# 141004_AriloTX_REV2_2_0_433MHZ_td.net
KiCad netlist of a schematic drawn in EAGLE
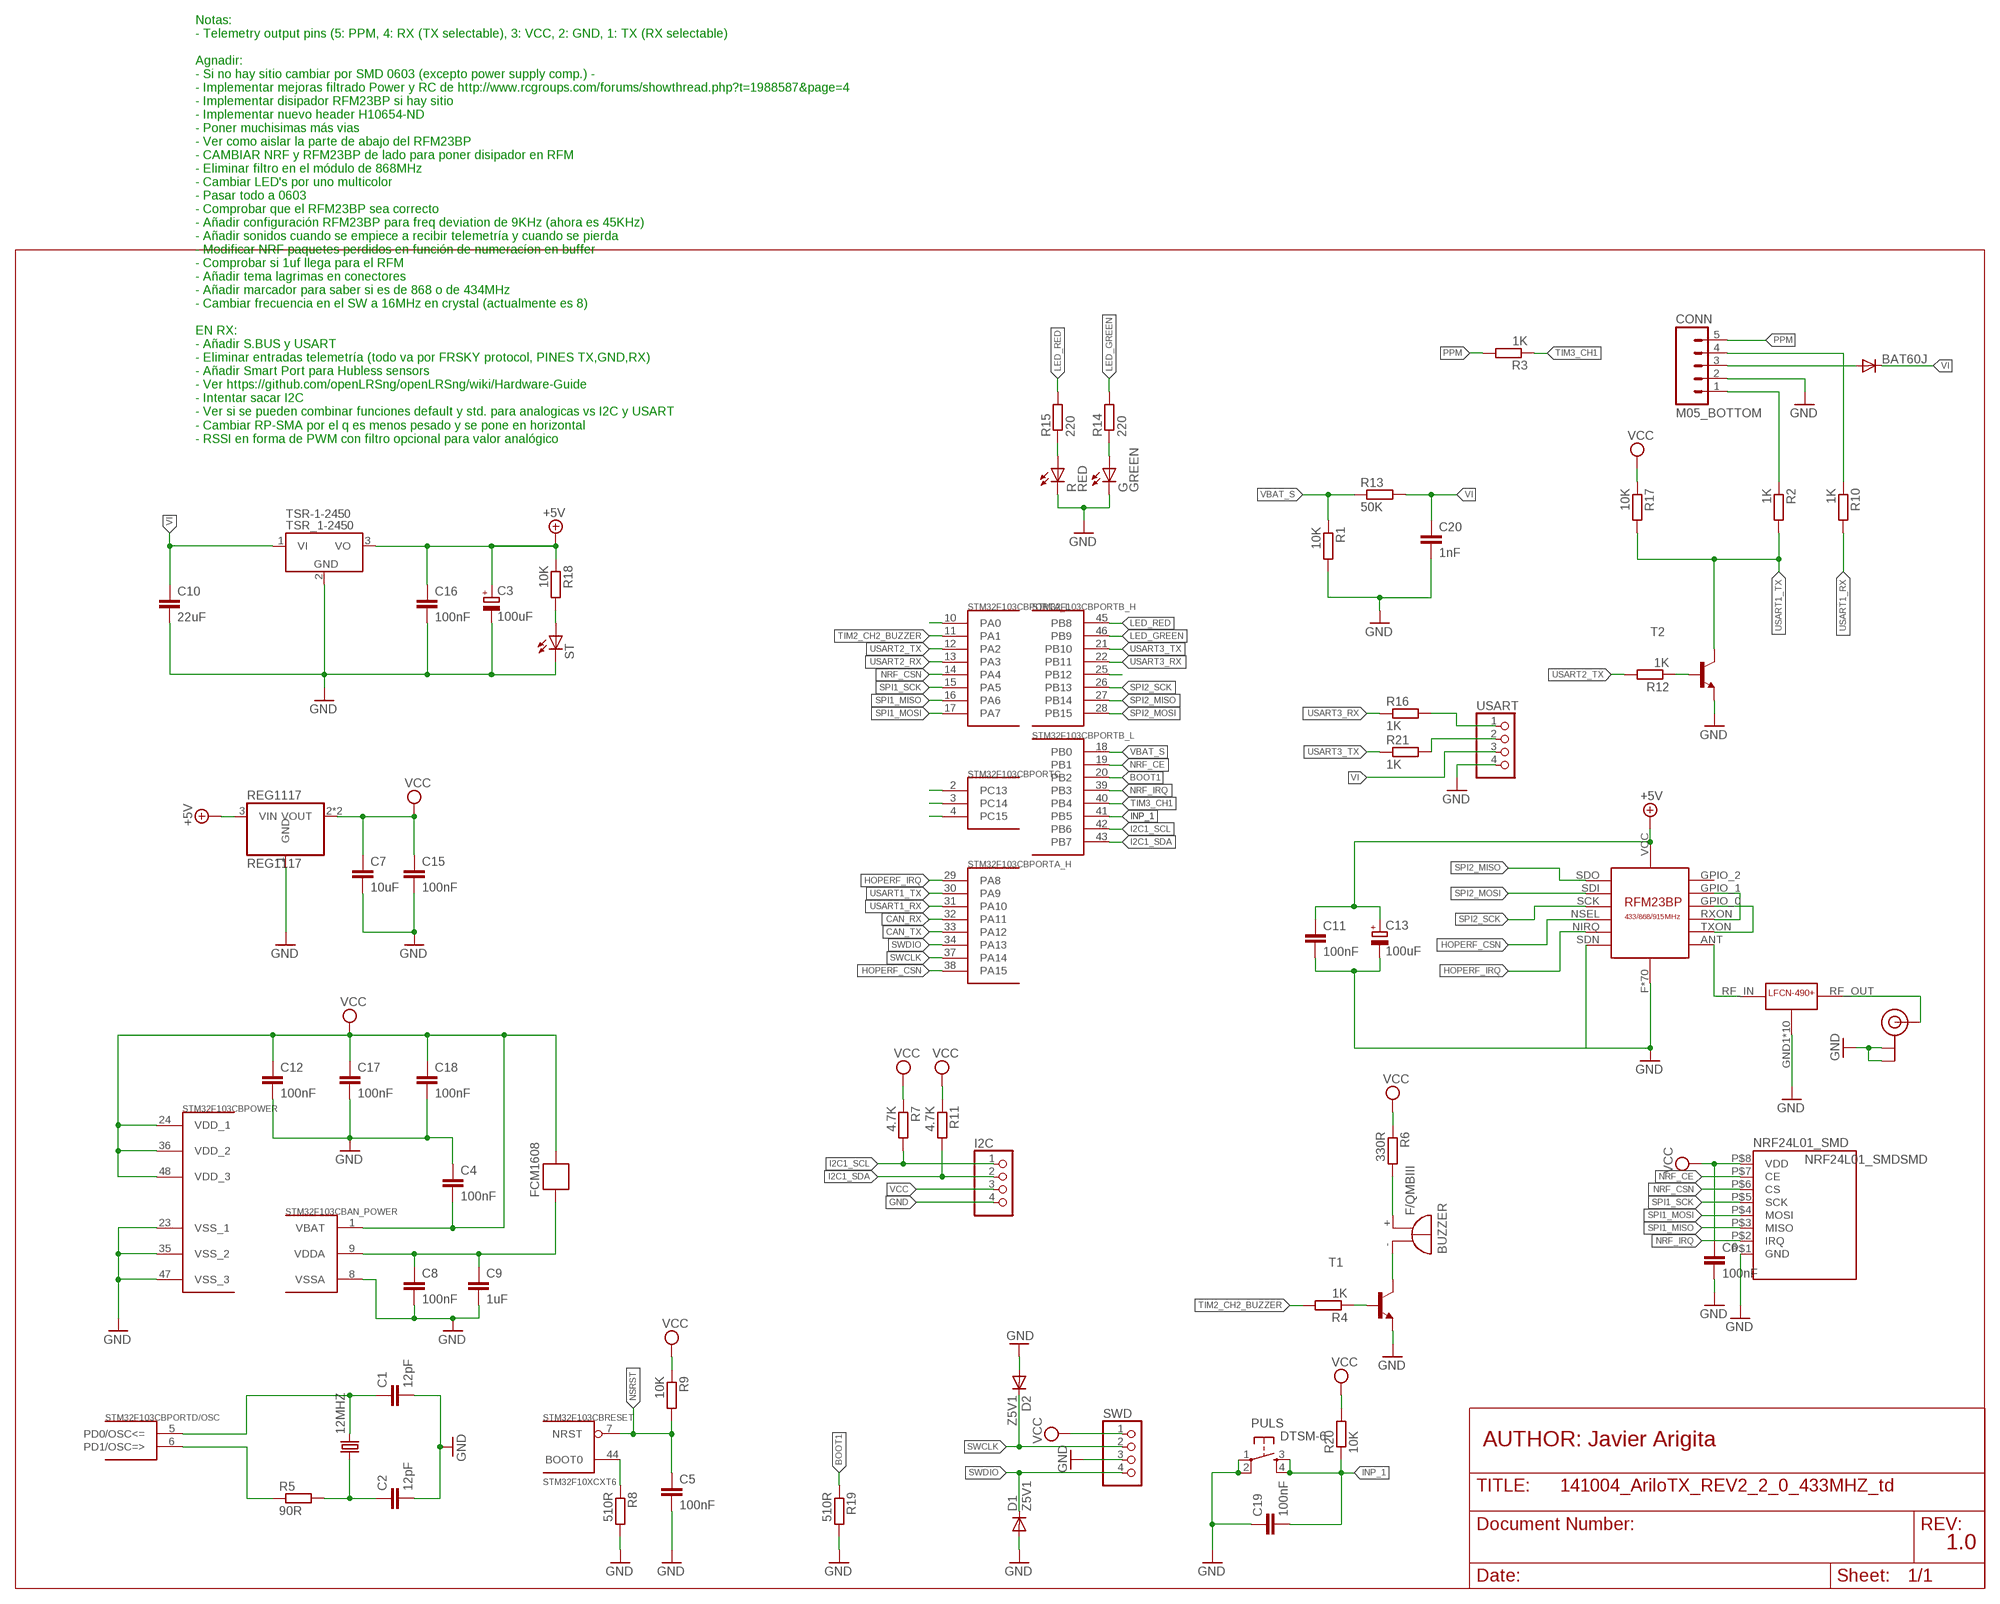
[diagram p0: schematic, sheet 1]

(export (version "E")
  (design (tool "Eeschema 10.0.6"))
  (components
    (comp (ref "12MHZ")
      (value "CRYSTAL5X3")
      (footprint "eagle-import:CRYSTAL-SMD-5X3")
      (libsource (lib "eagle-import") (part "CRYSTAL5X3"))
    )
    (comp (ref "BAT60J")
      (value "DIODE-SOD323-R")
      (footprint "eagle-import:SOD323-R")
      (libsource (lib "eagle-import") (part "DIODE-SOD323-R"))
    )
    (comp (ref "BUZZER")
      (value "F/QMBIII")
      (footprint "eagle-import:F_QMBIII")
      (libsource (lib "eagle-import") (part "F/QMBIII"))
    )
    (comp (ref "C1")
      (value "12pF")
      (footprint "eagle-import:C0603")
      (libsource (lib "eagle-import") (part "C-EUC0603"))
    )
    (comp (ref "C2")
      (value "12pF")
      (footprint "eagle-import:C0603")
      (libsource (lib "eagle-import") (part "C-EUC0603"))
    )
    (comp (ref "C3")
      (value "100uF")
      (footprint "eagle-import:SMC_B")
      (libsource (lib "eagle-import") (part "CPOL-EUSMCB"))
    )
    (comp (ref "C4")
      (value "100nF")
      (footprint "eagle-import:C0603")
      (libsource (lib "eagle-import") (part "C-EUC0603"))
    )
    (comp (ref "C5")
      (value "100nF")
      (footprint "eagle-import:C0603")
      (libsource (lib "eagle-import") (part "C-EUC0603"))
    )
    (comp (ref "C6")
      (value "100nF")
      (footprint "eagle-import:C0603")
      (libsource (lib "eagle-import") (part "C-EUC0603"))
    )
    (comp (ref "C7")
      (value "10uF")
      (footprint "eagle-import:C0805")
      (libsource (lib "eagle-import") (part "C-EUC0805"))
    )
    (comp (ref "C8")
      (value "100nF")
      (footprint "eagle-import:C0603")
      (libsource (lib "eagle-import") (part "C-EUC0603"))
    )
    (comp (ref "C9")
      (value "1uF")
      (footprint "eagle-import:C0603")
      (libsource (lib "eagle-import") (part "C-EUC0603"))
    )
    (comp (ref "C10")
      (value "22uF")
      (footprint "eagle-import:C3216")
      (libsource (lib "eagle-import") (part "resistor_C-EUC3216"))
    )
    (comp (ref "C11")
      (value "100nF")
      (footprint "eagle-import:C0603")
      (libsource (lib "eagle-import") (part "C-EUC0603"))
    )
    (comp (ref "C12")
      (value "100nF")
      (footprint "eagle-import:C0603")
      (libsource (lib "eagle-import") (part "C-EUC0603"))
    )
    (comp (ref "C13")
      (value "100uF")
      (footprint "eagle-import:SMC_B")
      (libsource (lib "eagle-import") (part "CPOL-EUSMCB"))
    )
    (comp (ref "C15")
      (value "100nF")
      (footprint "eagle-import:C0603")
      (libsource (lib "eagle-import") (part "C-EUC0603"))
    )
    (comp (ref "C16")
      (value "100nF")
      (footprint "eagle-import:C0603")
      (libsource (lib "eagle-import") (part "C-EUC0603"))
    )
    (comp (ref "C17")
      (value "100nF")
      (footprint "eagle-import:C0603")
      (libsource (lib "eagle-import") (part "C-EUC0603"))
    )
    (comp (ref "C18")
      (value "100nF")
      (footprint "eagle-import:C0603")
      (libsource (lib "eagle-import") (part "C-EUC0603"))
    )
    (comp (ref "C19")
      (value "100nF")
      (footprint "eagle-import:C0603")
      (libsource (lib "eagle-import") (part "C-EUC0603"))
    )
    (comp (ref "C20")
      (value "1nF")
      (footprint "eagle-import:C0603")
      (libsource (lib "eagle-import") (part "C-EUC0603"))
    )
    (comp (ref "CONN")
      (value "M05_BOTTOM")
      (footprint "eagle-import:M05_BOTTOM")
      (libsource (lib "eagle-import") (part "M05_BOTTOM"))
    )
    (comp (ref "D1")
      (value "Z5V1")
      (footprint "eagle-import:SOD323-R")
      (libsource (lib "eagle-import") (part "DIODE-SOD323-R"))
    )
    (comp (ref "D2")
      (value "Z5V1")
      (footprint "eagle-import:SOD323-R")
      (libsource (lib "eagle-import") (part "DIODE-SOD323-R"))
    )
    (comp (ref "FCM1608")
      (value "FERRITE-BEAD")
      (footprint "eagle-import:R0603")
      (libsource (lib "eagle-import") (part "FERRITE-BEAD"))
    )
    (comp (ref "G")
      (value "GREEN")
      (footprint "eagle-import:CHIP-LED0603")
      (libsource (lib "eagle-import") (part "LEDCHIP-LED0603"))
    )
    (comp (ref "I2C")
      (value "PINHD-1X4")
      (footprint "eagle-import:1X04")
      (libsource (lib "eagle-import") (part "PINHD-1X4"))
    )
    (comp (ref "LFCN490+")
      (value "LFCN490+")
      (footprint "eagle-import:LFCN490+")
      (libsource (lib "eagle-import") (part "LFCN490+"))
    )
    (comp (ref "NRF24L01_SMD")
      (value "NRF24L01_SMDSMD")
      (footprint "eagle-import:NRF24L01_SMD")
      (libsource (lib "eagle-import") (part "NRF24L01_SMDSMD"))
    )
    (comp (ref "PULS")
      (value "DTSM-6")
      (footprint "eagle-import:DTSM-6")
      (libsource (lib "eagle-import") (part "DTSM-6"))
    )
    (comp (ref "R")
      (value "RED")
      (footprint "eagle-import:CHIP-LED0603")
      (libsource (lib "eagle-import") (part "LEDCHIP-LED0603"))
    )
    (comp (ref "R1")
      (value "10K")
      (footprint "eagle-import:R0603")
      (libsource (lib "eagle-import") (part "R-EU_R0603"))
    )
    (comp (ref "R2")
      (value "1K")
      (footprint "eagle-import:R0603")
      (libsource (lib "eagle-import") (part "R-EU_R0603"))
    )
    (comp (ref "R3")
      (value "1K")
      (footprint "eagle-import:R0603")
      (libsource (lib "eagle-import") (part "R-EU_R0603"))
    )
    (comp (ref "R4")
      (value "1K")
      (footprint "eagle-import:R0603")
      (libsource (lib "eagle-import") (part "R-EU_R0603"))
    )
    (comp (ref "R5")
      (value "90R")
      (footprint "eagle-import:R0603")
      (libsource (lib "eagle-import") (part "R-EU_R0603"))
    )
    (comp (ref "R6")
      (value "330R")
      (footprint "eagle-import:R0603")
      (libsource (lib "eagle-import") (part "R-EU_R0603"))
    )
    (comp (ref "R7")
      (value "4.7K")
      (footprint "eagle-import:R0603")
      (libsource (lib "eagle-import") (part "R-EU_R0603"))
    )
    (comp (ref "R8")
      (value "510R")
      (footprint "eagle-import:R0603")
      (libsource (lib "eagle-import") (part "R-EU_R0603"))
    )
    (comp (ref "R9")
      (value "10K")
      (footprint "eagle-import:R0603")
      (libsource (lib "eagle-import") (part "R-EU_R0603"))
    )
    (comp (ref "R10")
      (value "1K")
      (footprint "eagle-import:R0603")
      (libsource (lib "eagle-import") (part "R-EU_R0603"))
    )
    (comp (ref "R11")
      (value "4.7K")
      (footprint "eagle-import:R0603")
      (libsource (lib "eagle-import") (part "R-EU_R0603"))
    )
    (comp (ref "R12")
      (value "1K")
      (footprint "eagle-import:R0603")
      (libsource (lib "eagle-import") (part "R-EU_R0603"))
    )
    (comp (ref "R13")
      (value "50K")
      (footprint "eagle-import:R0603")
      (libsource (lib "eagle-import") (part "R-EU_R0603"))
    )
    (comp (ref "R14")
      (value "220")
      (footprint "eagle-import:R0603")
      (libsource (lib "eagle-import") (part "R-EU_R0603"))
    )
    (comp (ref "R15")
      (value "220")
      (footprint "eagle-import:R0603")
      (libsource (lib "eagle-import") (part "R-EU_R0603"))
    )
    (comp (ref "R16")
      (value "1K")
      (footprint "eagle-import:R0603")
      (libsource (lib "eagle-import") (part "R-EU_R0603"))
    )
    (comp (ref "R17")
      (value "10K")
      (footprint "eagle-import:R0603")
      (libsource (lib "eagle-import") (part "R-EU_R0603"))
    )
    (comp (ref "R18")
      (value "10K")
      (footprint "eagle-import:R0603")
      (libsource (lib "eagle-import") (part "R-EU_R0603"))
    )
    (comp (ref "R19")
      (value "510R")
      (footprint "eagle-import:R0603")
      (libsource (lib "eagle-import") (part "R-EU_R0603"))
    )
    (comp (ref "R20")
      (value "10K")
      (footprint "eagle-import:R0603")
      (libsource (lib "eagle-import") (part "R-EU_R0603"))
    )
    (comp (ref "R21")
      (value "1K")
      (footprint "eagle-import:R0603")
      (libsource (lib "eagle-import") (part "R-EU_R0603"))
    )
    (comp (ref "REG1117")
      (value "REG1117")
      (footprint "eagle-import:SOT223")
      (libsource (lib "eagle-import") (part "REG1117"))
    )
    (comp (ref "ST")
      (value "LEDCHIP-LED0603")
      (footprint "eagle-import:CHIP-LED0603")
      (libsource (lib "eagle-import") (part "LEDCHIP-LED0603"))
    )
    (comp (ref "STM32F103CB")
      (value "STM32F10XCXT6")
      (footprint "eagle-import:TQFP48")
      (libsource (lib "eagle-import") (part "STM32F10XCXT6"))
    )
    (comp (ref "SWD")
      (value "PINHD-1X4")
      (footprint "eagle-import:1X04")
      (libsource (lib "eagle-import") (part "PINHD-1X4"))
    )
    (comp (ref "T1")
      (value "BC848-NPN-SOT23-BEC")
      (footprint "eagle-import:SOT23-BEC")
      (libsource (lib "eagle-import") (part "-NPN-SOT23-BECBC848"))
    )
    (comp (ref "T2")
      (value "BC848-NPN-SOT23-BEC")
      (footprint "eagle-import:SOT23-BEC")
      (libsource (lib "eagle-import") (part "-NPN-SOT23-BECBC848"))
    )
    (comp (ref "TSR-1-2450")
      (value "TSR_1-2450")
      (footprint "eagle-import:TSR-1")
      (libsource (lib "eagle-import") (part "TSR_1-2450"))
    )
    (comp (ref "U$1")
      (value "RFM23BP")
      (footprint "eagle-import:RFM23BP")
      (libsource (lib "eagle-import") (part "RFM23BP"))
    )
    (comp (ref "U.FL")
      (value "U.FL")
      (footprint "eagle-import:U.FL")
      (libsource (lib "eagle-import") (part "U.FL"))
    )
    (comp (ref "USART")
      (value "PINHD-1X4")
      (footprint "eagle-import:1X04")
      (libsource (lib "eagle-import") (part "PINHD-1X4"))
    )
  )
  (nets
    (net (code "1") (name "+5V") (class "Default")
      (node (ref "C11") (pin "1") (pinfunction "1_1") (pintype "passive"))
      (node (ref "C13") (pin "+") (pinfunction "+_+") (pintype "passive"))
      (node (ref "C16") (pin "1") (pinfunction "1_1") (pintype "passive"))
      (node (ref "C3") (pin "+") (pinfunction "+_+") (pintype "passive"))
      (node (ref "R18") (pin "1") (pinfunction "1_1") (pintype "passive"))
      (node (ref "REG1117") (pin "3") (pinfunction "VIN_3") (pintype "input"))
      (node (ref "TSR-1-2450") (pin "3") (pinfunction "VO_3") (pintype "power_in"))
      (node (ref "U$1") (pin "VCC") (pinfunction "VCC_VCC") (pintype "power_in"))
    )
    (net (code "2") (name "BOOT1") (class "Default")
      (node (ref "R19") (pin "1") (pinfunction "1_1") (pintype "passive"))
      (node (ref "STM32F103CB") (pin "20") (pinfunction "PB2_20") (pintype "bidirectional"))
    )
    (net (code "3") (name "CAN_RX") (class "Default")
      (node (ref "STM32F103CB") (pin "32") (pinfunction "PA11_32") (pintype "bidirectional"))
    )
    (net (code "4") (name "CAN_TX") (class "Default")
      (node (ref "STM32F103CB") (pin "33") (pinfunction "PA12_33") (pintype "bidirectional"))
    )
    (net (code "5") (name "GND") (class "Default")
      (node (ref "C1") (pin "2") (pinfunction "2_2") (pintype "passive"))
      (node (ref "C10") (pin "2") (pinfunction "2_2") (pintype "passive"))
      (node (ref "C11") (pin "2") (pinfunction "2_2") (pintype "passive"))
      (node (ref "C12") (pin "2") (pinfunction "2_2") (pintype "passive"))
      (node (ref "C13") (pin "-") (pinfunction "-_-") (pintype "passive"))
      (node (ref "C15") (pin "2") (pinfunction "2_2") (pintype "passive"))
      (node (ref "C16") (pin "2") (pinfunction "2_2") (pintype "passive"))
      (node (ref "C17") (pin "2") (pinfunction "2_2") (pintype "passive"))
      (node (ref "C18") (pin "2") (pinfunction "2_2") (pintype "passive"))
      (node (ref "C19") (pin "1") (pinfunction "1_1") (pintype "passive"))
      (node (ref "C2") (pin "2") (pinfunction "2_2") (pintype "passive"))
      (node (ref "C20") (pin "2") (pinfunction "2_2") (pintype "passive"))
      (node (ref "C3") (pin "-") (pinfunction "-_-") (pintype "passive"))
      (node (ref "C4") (pin "1") (pinfunction "1_1") (pintype "passive"))
      (node (ref "C5") (pin "2") (pinfunction "2_2") (pintype "passive"))
      (node (ref "C6") (pin "2") (pinfunction "2_2") (pintype "passive"))
      (node (ref "C7") (pin "2") (pinfunction "2_2") (pintype "passive"))
      (node (ref "C8") (pin "2") (pinfunction "2_2") (pintype "passive"))
      (node (ref "C9") (pin "2") (pinfunction "2_2") (pintype "passive"))
      (node (ref "CONN") (pin "2") (pinfunction "2_2") (pintype "passive"))
      (node (ref "D1") (pin "A") (pinfunction "A_A") (pintype "passive"))
      (node (ref "D2") (pin "A") (pinfunction "A_A") (pintype "passive"))
      (node (ref "G") (pin "C") (pinfunction "C_C") (pintype "passive"))
      (node (ref "I2C") (pin "4") (pinfunction "4_4") (pintype "passive"))
      (node (ref "LFCN490+") (pin "GND1") (pinfunction "GND_GND1") (pintype "bidirectional"))
      (node (ref "LFCN490+") (pin "GND10") (pinfunction "GND_GND10") (pintype "bidirectional"))
      (node (ref "LFCN490+") (pin "GND2") (pinfunction "GND_GND2") (pintype "bidirectional"))
      (node (ref "LFCN490+") (pin "GND3") (pinfunction "GND_GND3") (pintype "bidirectional"))
      (node (ref "LFCN490+") (pin "GND4") (pinfunction "GND_GND4") (pintype "bidirectional"))
      (node (ref "LFCN490+") (pin "GND5") (pinfunction "GND_GND5") (pintype "bidirectional"))
      (node (ref "LFCN490+") (pin "GND6") (pinfunction "GND_GND6") (pintype "bidirectional"))
      (node (ref "LFCN490+") (pin "GND7") (pinfunction "GND_GND7") (pintype "bidirectional"))
      (node (ref "LFCN490+") (pin "GND8") (pinfunction "GND_GND8") (pintype "bidirectional"))
      (node (ref "LFCN490+") (pin "GND9") (pinfunction "GND_GND9") (pintype "bidirectional"))
      (node (ref "NRF24L01_SMD") (pin "P$1") (pinfunction "GND_P$1") (pintype "power_in"))
      (node (ref "PULS") (pin "1") (pinfunction "1_1") (pintype "passive"))
      (node (ref "PULS") (pin "2") (pinfunction "2_2") (pintype "passive"))
      (node (ref "R") (pin "C") (pinfunction "C_C") (pintype "passive"))
      (node (ref "R1") (pin "2") (pinfunction "2_2") (pintype "passive"))
      (node (ref "R19") (pin "2") (pinfunction "2_2") (pintype "passive"))
      (node (ref "R8") (pin "2") (pinfunction "2_2") (pintype "passive"))
      (node (ref "REG1117") (pin "1") (pinfunction "GND_1") (pintype "power_in"))
      (node (ref "ST") (pin "C") (pinfunction "C_C") (pintype "passive"))
      (node (ref "STM32F103CB") (pin "23") (pinfunction "VSS_1_23") (pintype "power_in"))
      (node (ref "STM32F103CB") (pin "35") (pinfunction "VSS_2_35") (pintype "power_in"))
      (node (ref "STM32F103CB") (pin "47") (pinfunction "VSS_3_47") (pintype "power_in"))
      (node (ref "STM32F103CB") (pin "8") (pinfunction "VSSA_8") (pintype "power_in"))
      (node (ref "SWD") (pin "3") (pinfunction "3_3") (pintype "passive"))
      (node (ref "T1") (pin "E") (pinfunction "E_E") (pintype "passive"))
      (node (ref "T2") (pin "E") (pinfunction "E_E") (pintype "passive"))
      (node (ref "TSR-1-2450") (pin "2") (pinfunction "GND_2") (pintype "power_in"))
      (node (ref "U$1") (pin "F") (pinfunction "GND_F") (pintype "power_in"))
      (node (ref "U$1") (pin "F1") (pinfunction "GND_F1") (pintype "power_in"))
      (node (ref "U$1") (pin "F10") (pinfunction "GND_F10") (pintype "power_in"))
      (node (ref "U$1") (pin "F11") (pinfunction "GND_F11") (pintype "power_in"))
      (node (ref "U$1") (pin "F12") (pinfunction "GND_F12") (pintype "power_in"))
      (node (ref "U$1") (pin "F13") (pinfunction "GND_F13") (pintype "power_in"))
      (node (ref "U$1") (pin "F14") (pinfunction "GND_F14") (pintype "power_in"))
      (node (ref "U$1") (pin "F15") (pinfunction "GND_F15") (pintype "power_in"))
      (node (ref "U$1") (pin "F16") (pinfunction "GND_F16") (pintype "power_in"))
      (node (ref "U$1") (pin "F17") (pinfunction "GND_F17") (pintype "power_in"))
      (node (ref "U$1") (pin "F18") (pinfunction "GND_F18") (pintype "power_in"))
      (node (ref "U$1") (pin "F19") (pinfunction "GND_F19") (pintype "power_in"))
      (node (ref "U$1") (pin "F2") (pinfunction "GND_F2") (pintype "power_in"))
      (node (ref "U$1") (pin "F20") (pinfunction "GND_F20") (pintype "power_in"))
      (node (ref "U$1") (pin "F21") (pinfunction "GND_F21") (pintype "power_in"))
      (node (ref "U$1") (pin "F22") (pinfunction "GND_F22") (pintype "power_in"))
      (node (ref "U$1") (pin "F23") (pinfunction "GND_F23") (pintype "power_in"))
      (node (ref "U$1") (pin "F24") (pinfunction "GND_F24") (pintype "power_in"))
      (node (ref "U$1") (pin "F25") (pinfunction "GND_F25") (pintype "power_in"))
      (node (ref "U$1") (pin "F26") (pinfunction "GND_F26") (pintype "power_in"))
      (node (ref "U$1") (pin "F27") (pinfunction "GND_F27") (pintype "power_in"))
      (node (ref "U$1") (pin "F28") (pinfunction "GND_F28") (pintype "power_in"))
      (node (ref "U$1") (pin "F29") (pinfunction "GND_F29") (pintype "power_in"))
      (node (ref "U$1") (pin "F3") (pinfunction "GND_F3") (pintype "power_in"))
      (node (ref "U$1") (pin "F30") (pinfunction "GND_F30") (pintype "power_in"))
      (node (ref "U$1") (pin "F31") (pinfunction "GND_F31") (pintype "power_in"))
      (node (ref "U$1") (pin "F32") (pinfunction "GND_F32") (pintype "power_in"))
      (node (ref "U$1") (pin "F33") (pinfunction "GND_F33") (pintype "power_in"))
      (node (ref "U$1") (pin "F34") (pinfunction "GND_F34") (pintype "power_in"))
      (node (ref "U$1") (pin "F35") (pinfunction "GND_F35") (pintype "power_in"))
      (node (ref "U$1") (pin "F36") (pinfunction "GND_F36") (pintype "power_in"))
      (node (ref "U$1") (pin "F37") (pinfunction "GND_F37") (pintype "power_in"))
      (node (ref "U$1") (pin "F38") (pinfunction "GND_F38") (pintype "power_in"))
      (node (ref "U$1") (pin "F39") (pinfunction "GND_F39") (pintype "power_in"))
      (node (ref "U$1") (pin "F4") (pinfunction "GND_F4") (pintype "power_in"))
      (node (ref "U$1") (pin "F40") (pinfunction "GND_F40") (pintype "power_in"))
      (node (ref "U$1") (pin "F41") (pinfunction "GND_F41") (pintype "power_in"))
      (node (ref "U$1") (pin "F42") (pinfunction "GND_F42") (pintype "power_in"))
      (node (ref "U$1") (pin "F43") (pinfunction "GND_F43") (pintype "power_in"))
      (node (ref "U$1") (pin "F44") (pinfunction "GND_F44") (pintype "power_in"))
      (node (ref "U$1") (pin "F45") (pinfunction "GND_F45") (pintype "power_in"))
      (node (ref "U$1") (pin "F46") (pinfunction "GND_F46") (pintype "power_in"))
      (node (ref "U$1") (pin "F47") (pinfunction "GND_F47") (pintype "power_in"))
      (node (ref "U$1") (pin "F48") (pinfunction "GND_F48") (pintype "power_in"))
      (node (ref "U$1") (pin "F49") (pinfunction "GND_F49") (pintype "power_in"))
      (node (ref "U$1") (pin "F5") (pinfunction "GND_F5") (pintype "power_in"))
      (node (ref "U$1") (pin "F50") (pinfunction "GND_F50") (pintype "power_in"))
      (node (ref "U$1") (pin "F51") (pinfunction "GND_F51") (pintype "power_in"))
      (node (ref "U$1") (pin "F52") (pinfunction "GND_F52") (pintype "power_in"))
      (node (ref "U$1") (pin "F53") (pinfunction "GND_F53") (pintype "power_in"))
      (node (ref "U$1") (pin "F54") (pinfunction "GND_F54") (pintype "power_in"))
      (node (ref "U$1") (pin "F55") (pinfunction "GND_F55") (pintype "power_in"))
      (node (ref "U$1") (pin "F56") (pinfunction "GND_F56") (pintype "power_in"))
      (node (ref "U$1") (pin "F57") (pinfunction "GND_F57") (pintype "power_in"))
      (node (ref "U$1") (pin "F58") (pinfunction "GND_F58") (pintype "power_in"))
      (node (ref "U$1") (pin "F59") (pinfunction "GND_F59") (pintype "power_in"))
      (node (ref "U$1") (pin "F6") (pinfunction "GND_F6") (pintype "power_in"))
      (node (ref "U$1") (pin "F60") (pinfunction "GND_F60") (pintype "power_in"))
      (node (ref "U$1") (pin "F61") (pinfunction "GND_F61") (pintype "power_in"))
      (node (ref "U$1") (pin "F62") (pinfunction "GND_F62") (pintype "power_in"))
      (node (ref "U$1") (pin "F63") (pinfunction "GND_F63") (pintype "power_in"))
      (node (ref "U$1") (pin "F64") (pinfunction "GND_F64") (pintype "power_in"))
      (node (ref "U$1") (pin "F65") (pinfunction "GND_F65") (pintype "power_in"))
      (node (ref "U$1") (pin "F7") (pinfunction "GND_F7") (pintype "power_in"))
      (node (ref "U$1") (pin "F8") (pinfunction "GND_F8") (pintype "power_in"))
      (node (ref "U$1") (pin "F9") (pinfunction "GND_F9") (pintype "power_in"))
      (node (ref "U$1") (pin "GND1") (pinfunction "GND_GND1") (pintype "power_in"))
      (node (ref "U$1") (pin "GND2") (pinfunction "GND_GND2") (pintype "power_in"))
      (node (ref "U$1") (pin "GND3") (pinfunction "GND_GND3") (pintype "power_in"))
      (node (ref "U$1") (pin "GND_HEAT") (pinfunction "GND_GND_HEAT") (pintype "power_in"))
      (node (ref "U$1") (pin "SDN") (pinfunction "SDN_SDN") (pintype "bidirectional"))
      (node (ref "U.FL") (pin "P$1") (pinfunction "GND_P$1") (pintype "bidirectional"))
      (node (ref "U.FL") (pin "P$2") (pinfunction "GND_P$2") (pintype "bidirectional"))
      (node (ref "USART") (pin "4") (pinfunction "4_4") (pintype "passive"))
    )
    (net (code "6") (name "HOPERF_CSN") (class "Default")
      (node (ref "STM32F103CB") (pin "38") (pinfunction "PA15_38") (pintype "bidirectional"))
      (node (ref "U$1") (pin "NSEL") (pinfunction "NSEL_NSEL") (pintype "bidirectional"))
    )
    (net (code "7") (name "HOPERF_IRQ") (class "Default")
      (node (ref "STM32F103CB") (pin "29") (pinfunction "PA8_29") (pintype "bidirectional"))
      (node (ref "U$1") (pin "NIRQ") (pinfunction "NIRQ_NIRQ") (pintype "bidirectional"))
    )
    (net (code "8") (name "I2C1_SCL") (class "Default")
      (node (ref "I2C") (pin "1") (pinfunction "1_1") (pintype "passive"))
      (node (ref "R7") (pin "2") (pinfunction "2_2") (pintype "passive"))
      (node (ref "STM32F103CB") (pin "42") (pinfunction "PB6_42") (pintype "bidirectional"))
    )
    (net (code "9") (name "I2C1_SDA") (class "Default")
      (node (ref "I2C") (pin "2") (pinfunction "2_2") (pintype "passive"))
      (node (ref "R11") (pin "2") (pinfunction "2_2") (pintype "passive"))
      (node (ref "STM32F103CB") (pin "43") (pinfunction "PB7_43") (pintype "bidirectional"))
    )
    (net (code "10") (name "INP_1") (class "Default")
      (node (ref "C19") (pin "2") (pinfunction "2_2") (pintype "passive"))
      (node (ref "PULS") (pin "3") (pinfunction "3_3") (pintype "passive"))
      (node (ref "PULS") (pin "4") (pinfunction "4_4") (pintype "passive"))
      (node (ref "R20") (pin "1") (pinfunction "1_1") (pintype "passive"))
      (node (ref "STM32F103CB") (pin "41") (pinfunction "PB5_41") (pintype "bidirectional"))
    )
    (net (code "11") (name "LED_GREEN") (class "Default")
      (node (ref "R14") (pin "2") (pinfunction "2_2") (pintype "passive"))
      (node (ref "STM32F103CB") (pin "46") (pinfunction "PB9_46") (pintype "bidirectional"))
    )
    (net (code "12") (name "LED_RED") (class "Default")
      (node (ref "R15") (pin "2") (pinfunction "2_2") (pintype "passive"))
      (node (ref "STM32F103CB") (pin "45") (pinfunction "PB8_45") (pintype "bidirectional"))
    )
    (net (code "13") (name "NRF_CE") (class "Default")
      (node (ref "NRF24L01_SMD") (pin "P$7") (pinfunction "CE_P$7") (pintype "input"))
      (node (ref "STM32F103CB") (pin "19") (pinfunction "PB1_19") (pintype "bidirectional"))
    )
    (net (code "14") (name "NRF_CSN") (class "Default")
      (node (ref "NRF24L01_SMD") (pin "P$6") (pinfunction "CS_P$6") (pintype "input"))
      (node (ref "STM32F103CB") (pin "14") (pinfunction "PA4_14") (pintype "bidirectional"))
    )
    (net (code "15") (name "NRF_IRQ") (class "Default")
      (node (ref "NRF24L01_SMD") (pin "P$2") (pinfunction "IRQ_P$2") (pintype "output"))
      (node (ref "STM32F103CB") (pin "39") (pinfunction "PB3_39") (pintype "bidirectional"))
    )
    (net (code "16") (name "NSRST") (class "Default")
      (node (ref "C5") (pin "1") (pinfunction "1_1") (pintype "passive"))
      (node (ref "R9") (pin "2") (pinfunction "2_2") (pintype "passive"))
      (node (ref "STM32F103CB") (pin "7") (pinfunction "NRST_7") (pintype "input"))
    )
    (net (code "17") (name "Net-(12MHZ-2)") (class "Default")
      (node (ref "12MHZ") (pin "3") (pinfunction "2_3") (pintype "passive"))
      (node (ref "C1") (pin "1") (pinfunction "1_1") (pintype "passive"))
      (node (ref "STM32F103CB") (pin "5") (pinfunction "PD0/OSC<=_5") (pintype "bidirectional"))
    )
    (net (code "18") (name "Net-(12MHZ-Pad1)") (class "Default")
      (node (ref "12MHZ") (pin "1") (pinfunction "1_1") (pintype "passive"))
      (node (ref "C2") (pin "1") (pinfunction "1_1") (pintype "passive"))
      (node (ref "R5") (pin "2") (pinfunction "2_2") (pintype "passive"))
    )
    (net (code "19") (name "Net-(BAT60J-PadA)") (class "Default")
      (node (ref "BAT60J") (pin "A") (pinfunction "A_A") (pintype "passive"))
      (node (ref "CONN") (pin "3") (pinfunction "3_3") (pintype "passive"))
    )
    (net (code "20") (name "Net-(BUZZER-+)") (class "Default")
      (node (ref "BUZZER") (pin "-") (pinfunction "+_-") (pintype "passive"))
      (node (ref "T1") (pin "C") (pinfunction "C_C") (pintype "passive"))
    )
    (net (code "21") (name "Net-(BUZZER--)") (class "Default")
      (node (ref "BUZZER") (pin "+") (pinfunction "-_+") (pintype "passive"))
      (node (ref "R6") (pin "2") (pinfunction "2_2") (pintype "passive"))
    )
    (net (code "22") (name "Net-(CONN-Pad1)") (class "Default")
      (node (ref "CONN") (pin "1") (pinfunction "1_1") (pintype "passive"))
      (node (ref "R2") (pin "1") (pinfunction "1_1") (pintype "passive"))
    )
    (net (code "23") (name "Net-(CONN-Pad4)") (class "Default")
      (node (ref "CONN") (pin "4") (pinfunction "4_4") (pintype "passive"))
      (node (ref "R10") (pin "1") (pinfunction "1_1") (pintype "passive"))
    )
    (net (code "24") (name "Net-(FCM1608-P$2)") (class "Default")
      (node (ref "C8") (pin "1") (pinfunction "1_1") (pintype "passive"))
      (node (ref "C9") (pin "1") (pinfunction "1_1") (pintype "passive"))
      (node (ref "FCM1608") (pin "2") (pinfunction "P$2_2") (pintype "bidirectional"))
      (node (ref "STM32F103CB") (pin "9") (pinfunction "VDDA_9") (pintype "power_in"))
    )
    (net (code "25") (name "Net-(G-PadA)") (class "Default")
      (node (ref "G") (pin "A") (pinfunction "A_A") (pintype "passive"))
      (node (ref "R14") (pin "1") (pinfunction "1_1") (pintype "passive"))
    )
    (net (code "26") (name "Net-(LFCN490+-RF_INP)") (class "Default")
      (node (ref "LFCN490+") (pin "RF_IN") (pinfunction "RF_INP_RF_IN") (pintype "bidirectional"))
      (node (ref "U$1") (pin "ANT") (pinfunction "ANT_ANT") (pintype "bidirectional"))
    )
    (net (code "27") (name "Net-(LFCN490+-RF_OUTP)") (class "Default")
      (node (ref "LFCN490+") (pin "RF_OUT") (pinfunction "RF_OUTP_RF_OUT") (pintype "bidirectional"))
      (node (ref "U.FL") (pin "P$3") (pinfunction "SIGNAL_P$3") (pintype "bidirectional"))
    )
    (net (code "28") (name "Net-(R-PadA)") (class "Default")
      (node (ref "R") (pin "A") (pinfunction "A_A") (pintype "passive"))
      (node (ref "R15") (pin "1") (pinfunction "1_1") (pintype "passive"))
    )
    (net (code "29") (name "Net-(R4-Pad1)") (class "Default")
      (node (ref "R4") (pin "1") (pinfunction "1_1") (pintype "passive"))
      (node (ref "T1") (pin "B") (pinfunction "B_B") (pintype "passive"))
    )
    (net (code "30") (name "Net-(R12-Pad1)") (class "Default")
      (node (ref "R12") (pin "1") (pinfunction "1_1") (pintype "passive"))
      (node (ref "T2") (pin "B") (pinfunction "B_B") (pintype "passive"))
    )
    (net (code "31") (name "Net-(R16-Pad2)") (class "Default")
      (node (ref "R16") (pin "2") (pinfunction "2_2") (pintype "passive"))
      (node (ref "USART") (pin "1") (pinfunction "1_1") (pintype "passive"))
    )
    (net (code "32") (name "Net-(R18-Pad2)") (class "Default")
      (node (ref "R18") (pin "2") (pinfunction "2_2") (pintype "passive"))
      (node (ref "ST") (pin "A") (pinfunction "A_A") (pintype "passive"))
    )
    (net (code "33") (name "Net-(R21-Pad2)") (class "Default")
      (node (ref "R21") (pin "2") (pinfunction "2_2") (pintype "passive"))
      (node (ref "USART") (pin "2") (pinfunction "2_2") (pintype "passive"))
    )
    (net (code "34") (name "Net-(STM32F103CBG-PD1{slash}OSC=>)") (class "Default")
      (node (ref "R5") (pin "1") (pinfunction "1_1") (pintype "passive"))
      (node (ref "STM32F103CB") (pin "6") (pinfunction "PD1/OSC=>_6") (pintype "bidirectional"))
    )
    (net (code "35") (name "Net-(STM32F103CBI-BOOT0)") (class "Default")
      (node (ref "R8") (pin "1") (pinfunction "1_1") (pintype "passive"))
      (node (ref "STM32F103CB") (pin "44") (pinfunction "BOOT0_44") (pintype "input"))
    )
    (net (code "36") (name "Net-(U$1-PadGPIO_0)") (class "Default")
      (node (ref "U$1") (pin "GPIO_0") (pinfunction "GPIO_0_GPIO_0") (pintype "bidirectional"))
      (node (ref "U$1") (pin "TXON") (pinfunction "TXON_TXON") (pintype "bidirectional"))
    )
    (net (code "37") (name "Net-(U$1-PadGPIO_1)") (class "Default")
      (node (ref "U$1") (pin "GPIO_1") (pinfunction "GPIO_1_GPIO_1") (pintype "bidirectional"))
      (node (ref "U$1") (pin "RXON") (pinfunction "RXON_RXON") (pintype "bidirectional"))
    )
    (net (code "38") (name "PPM") (class "Default")
      (node (ref "CONN") (pin "5") (pinfunction "5_5") (pintype "passive"))
      (node (ref "R3") (pin "2") (pinfunction "2_2") (pintype "passive"))
    )
    (net (code "39") (name "SPI1_MISO") (class "Default")
      (node (ref "NRF24L01_SMD") (pin "P$3") (pinfunction "MISO_P$3") (pintype "output"))
      (node (ref "STM32F103CB") (pin "16") (pinfunction "PA6_16") (pintype "bidirectional"))
    )
    (net (code "40") (name "SPI1_MOSI") (class "Default")
      (node (ref "NRF24L01_SMD") (pin "P$4") (pinfunction "MOSI_P$4") (pintype "input"))
      (node (ref "STM32F103CB") (pin "17") (pinfunction "PA7_17") (pintype "bidirectional"))
    )
    (net (code "41") (name "SPI1_SCK") (class "Default")
      (node (ref "NRF24L01_SMD") (pin "P$5") (pinfunction "SCK_P$5") (pintype "input"))
      (node (ref "STM32F103CB") (pin "15") (pinfunction "PA5_15") (pintype "bidirectional"))
    )
    (net (code "42") (name "SPI2_MISO") (class "Default")
      (node (ref "STM32F103CB") (pin "27") (pinfunction "PB14_27") (pintype "bidirectional"))
      (node (ref "U$1") (pin "SDO") (pinfunction "SDO_SDO") (pintype "bidirectional"))
    )
    (net (code "43") (name "SPI2_MOSI") (class "Default")
      (node (ref "STM32F103CB") (pin "28") (pinfunction "PB15_28") (pintype "bidirectional"))
      (node (ref "U$1") (pin "SDI") (pinfunction "SDI_SDI") (pintype "bidirectional"))
    )
    (net (code "44") (name "SPI2_SCK") (class "Default")
      (node (ref "STM32F103CB") (pin "26") (pinfunction "PB13_26") (pintype "bidirectional"))
      (node (ref "U$1") (pin "SCK") (pinfunction "SCK_SCK") (pintype "bidirectional"))
    )
    (net (code "45") (name "SWCLK") (class "Default")
      (node (ref "D2") (pin "C") (pinfunction "C_C") (pintype "passive"))
      (node (ref "STM32F103CB") (pin "37") (pinfunction "PA14_37") (pintype "bidirectional"))
      (node (ref "SWD") (pin "2") (pinfunction "2_2") (pintype "passive"))
    )
    (net (code "46") (name "SWDIO") (class "Default")
      (node (ref "D1") (pin "C") (pinfunction "C_C") (pintype "passive"))
      (node (ref "STM32F103CB") (pin "34") (pinfunction "PA13_34") (pintype "bidirectional"))
      (node (ref "SWD") (pin "4") (pinfunction "4_4") (pintype "passive"))
    )
    (net (code "47") (name "TIM2_CH2_BUZZER") (class "Default")
      (node (ref "R4") (pin "2") (pinfunction "2_2") (pintype "passive"))
      (node (ref "STM32F103CB") (pin "11") (pinfunction "PA1_11") (pintype "bidirectional"))
    )
    (net (code "48") (name "TIM3_CH1") (class "Default")
      (node (ref "R3") (pin "1") (pinfunction "1_1") (pintype "passive"))
      (node (ref "STM32F103CB") (pin "40") (pinfunction "PB4_40") (pintype "bidirectional"))
    )
    (net (code "49") (name "USART1_RX") (class "Default")
      (node (ref "R10") (pin "2") (pinfunction "2_2") (pintype "passive"))
      (node (ref "STM32F103CB") (pin "31") (pinfunction "PA10_31") (pintype "bidirectional"))
    )
    (net (code "50") (name "USART1_TX") (class "Default")
      (node (ref "R17") (pin "2") (pinfunction "2_2") (pintype "passive"))
      (node (ref "R2") (pin "2") (pinfunction "2_2") (pintype "passive"))
      (node (ref "STM32F103CB") (pin "30") (pinfunction "PA9_30") (pintype "bidirectional"))
      (node (ref "T2") (pin "C") (pinfunction "C_C") (pintype "passive"))
    )
    (net (code "51") (name "USART2_RX") (class "Default")
      (node (ref "STM32F103CB") (pin "13") (pinfunction "PA3_13") (pintype "bidirectional"))
    )
    (net (code "52") (name "USART2_TX") (class "Default")
      (node (ref "R12") (pin "2") (pinfunction "2_2") (pintype "passive"))
      (node (ref "STM32F103CB") (pin "12") (pinfunction "PA2_12") (pintype "bidirectional"))
    )
    (net (code "53") (name "USART3_RX") (class "Default")
      (node (ref "R16") (pin "1") (pinfunction "1_1") (pintype "passive"))
      (node (ref "STM32F103CB") (pin "22") (pinfunction "PB11_22") (pintype "bidirectional"))
    )
    (net (code "54") (name "USART3_TX") (class "Default")
      (node (ref "R21") (pin "1") (pinfunction "1_1") (pintype "passive"))
      (node (ref "STM32F103CB") (pin "21") (pinfunction "PB10_21") (pintype "bidirectional"))
    )
    (net (code "55") (name "VBAT_S") (class "Default")
      (node (ref "R1") (pin "1") (pinfunction "1_1") (pintype "passive"))
      (node (ref "R13") (pin "1") (pinfunction "1_1") (pintype "passive"))
      (node (ref "STM32F103CB") (pin "18") (pinfunction "PB0_18") (pintype "bidirectional"))
    )
    (net (code "56") (name "VCC") (class "Default")
      (node (ref "C12") (pin "1") (pinfunction "1_1") (pintype "passive"))
      (node (ref "C15") (pin "1") (pinfunction "1_1") (pintype "passive"))
      (node (ref "C17") (pin "1") (pinfunction "1_1") (pintype "passive"))
      (node (ref "C18") (pin "1") (pinfunction "1_1") (pintype "passive"))
      (node (ref "C4") (pin "2") (pinfunction "2_2") (pintype "passive"))
      (node (ref "C6") (pin "1") (pinfunction "1_1") (pintype "passive"))
      (node (ref "C7") (pin "1") (pinfunction "1_1") (pintype "passive"))
      (node (ref "FCM1608") (pin "1") (pinfunction "P$1_1") (pintype "bidirectional"))
      (node (ref "I2C") (pin "3") (pinfunction "3_3") (pintype "passive"))
      (node (ref "NRF24L01_SMD") (pin "P$8") (pinfunction "VDD_P$8") (pintype "bidirectional"))
      (node (ref "R11") (pin "1") (pinfunction "1_1") (pintype "passive"))
      (node (ref "R17") (pin "1") (pinfunction "1_1") (pintype "passive"))
      (node (ref "R20") (pin "2") (pinfunction "2_2") (pintype "passive"))
      (node (ref "R6") (pin "1") (pinfunction "1_1") (pintype "passive"))
      (node (ref "R7") (pin "1") (pinfunction "1_1") (pintype "passive"))
      (node (ref "R9") (pin "1") (pinfunction "1_1") (pintype "passive"))
      (node (ref "REG1117") (pin "2") (pinfunction "VOUT_2") (pintype "power_in"))
      (node (ref "REG1117") (pin "4") (pinfunction "VOUT_4") (pintype "power_in"))
      (node (ref "STM32F103CB") (pin "1") (pinfunction "VBAT_1") (pintype "power_in"))
      (node (ref "STM32F103CB") (pin "24") (pinfunction "VDD_1_24") (pintype "power_in"))
      (node (ref "STM32F103CB") (pin "36") (pinfunction "VDD_2_36") (pintype "power_in"))
      (node (ref "STM32F103CB") (pin "48") (pinfunction "VDD_3_48") (pintype "power_in"))
      (node (ref "SWD") (pin "1") (pinfunction "1_1") (pintype "passive"))
    )
    (net (code "57") (name "VI") (class "Default")
      (node (ref "BAT60J") (pin "C") (pinfunction "C_C") (pintype "passive"))
      (node (ref "C10") (pin "1") (pinfunction "1_1") (pintype "passive"))
      (node (ref "C20") (pin "1") (pinfunction "1_1") (pintype "passive"))
      (node (ref "R13") (pin "2") (pinfunction "2_2") (pintype "passive"))
      (node (ref "TSR-1-2450") (pin "1") (pinfunction "VI_1") (pintype "power_in"))
      (node (ref "USART") (pin "3") (pinfunction "3_3") (pintype "passive"))
    )
    (net (code "58") (name "unconnected-(STM32F103CBC-PA0-Pad10)") (class "Default")
      (node (ref "STM32F103CB") (pin "10") (pinfunction "PA0_10") (pintype "bidirectional"))
    )
    (net (code "59") (name "unconnected-(STM32F103CBD-PB12-Pad25)") (class "Default")
      (node (ref "STM32F103CB") (pin "25") (pinfunction "PB12_25") (pintype "bidirectional"))
    )
    (net (code "60") (name "unconnected-(STM32F103CBF-PC13-Pad2)") (class "Default")
      (node (ref "STM32F103CB") (pin "2") (pinfunction "PC13_2") (pintype "bidirectional"))
    )
    (net (code "61") (name "unconnected-(STM32F103CBF-PC14-Pad3)") (class "Default")
      (node (ref "STM32F103CB") (pin "3") (pinfunction "PC14_3") (pintype "bidirectional"))
    )
    (net (code "62") (name "unconnected-(STM32F103CBF-PC15-Pad4)") (class "Default")
      (node (ref "STM32F103CB") (pin "4") (pinfunction "PC15_4") (pintype "bidirectional"))
    )
    (net (code "63") (name "unconnected-(U$1-PadGPIO_2)") (class "Default")
      (node (ref "U$1") (pin "GPIO_2") (pinfunction "GPIO_2_GPIO_2") (pintype "bidirectional"))
    )
  )
)
